# ENGI301_Project_Actual.net
KiCad netlist of a schematic drawn in EAGLE
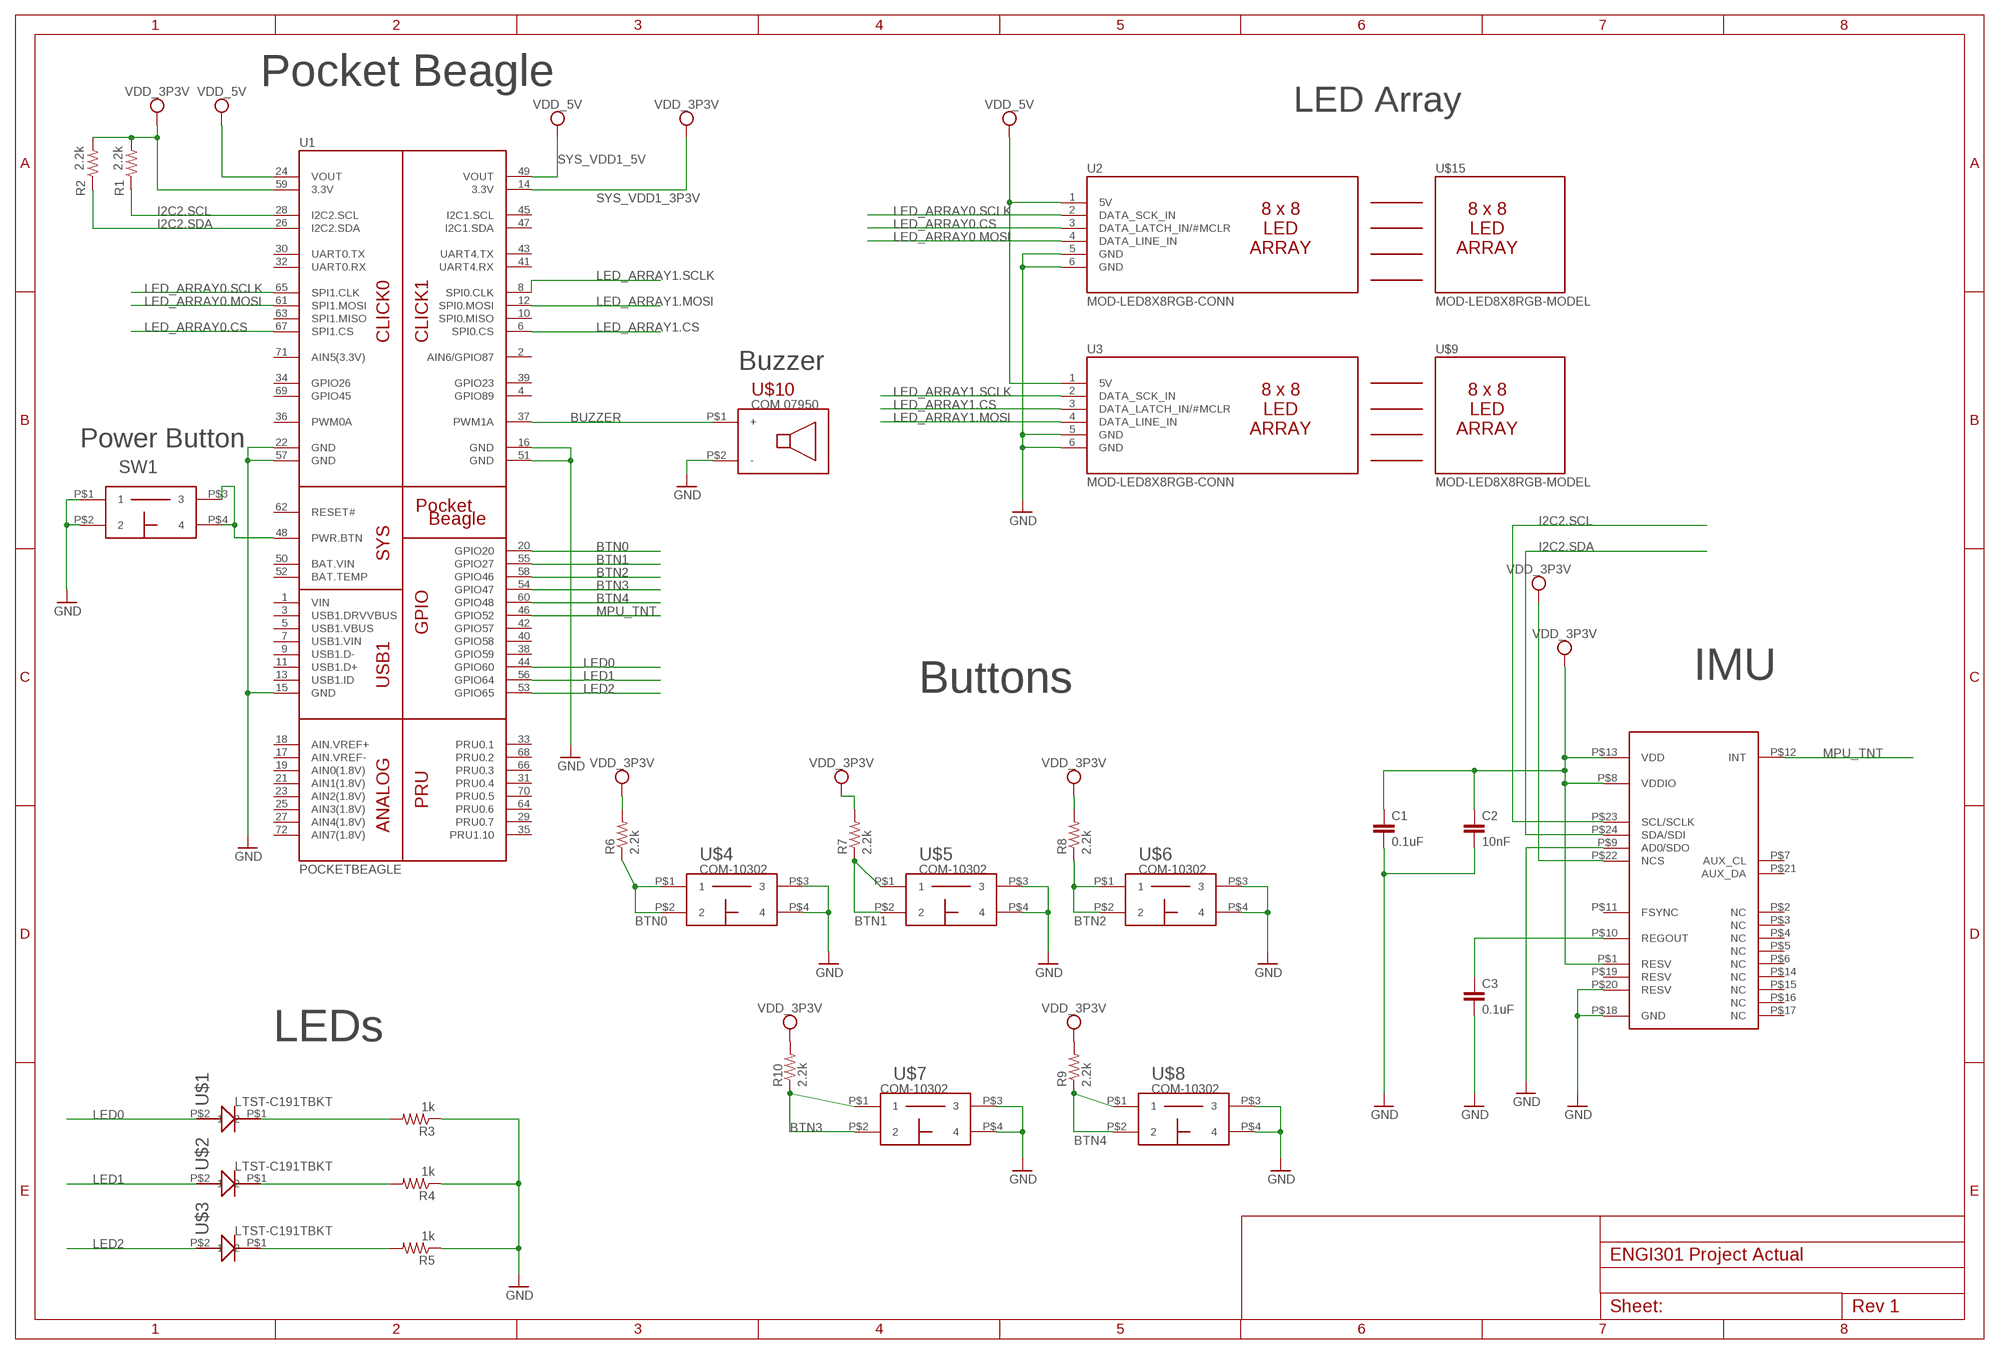
[diagram p0: schematic, sheet 1]

(export (version "E")
  (design (tool "Eeschema 10.0.6"))
  (components
    (comp (ref "C1")
      (value "0.1uF")
      (footprint "eagle-import:C0603")
      (libsource (lib "eagle-import") (part "C_C0603"))
    )
    (comp (ref "C2")
      (value "10nF")
      (footprint "eagle-import:C0603")
      (libsource (lib "eagle-import") (part "C_C0603"))
    )
    (comp (ref "C3")
      (value "0.1uF")
      (footprint "eagle-import:C0603")
      (libsource (lib "eagle-import") (part "C_C0603"))
    )
    (comp (ref "R1")
      (value "2.2k")
      (footprint "eagle-import:R0603")
      (libsource (lib "eagle-import") (part "R_R0603"))
    )
    (comp (ref "R2")
      (value "2.2k")
      (footprint "eagle-import:R0603")
      (libsource (lib "eagle-import") (part "R_R0603"))
    )
    (comp (ref "R3")
      (value "1k")
      (footprint "eagle-import:R0603")
      (libsource (lib "eagle-import") (part "R_R0603"))
    )
    (comp (ref "R4")
      (value "1k")
      (footprint "eagle-import:R0603")
      (libsource (lib "eagle-import") (part "R_R0603"))
    )
    (comp (ref "R5")
      (value "1k")
      (footprint "eagle-import:R0603")
      (libsource (lib "eagle-import") (part "R_R0603"))
    )
    (comp (ref "R6")
      (value "2.2k")
      (footprint "eagle-import:R0603")
      (libsource (lib "eagle-import") (part "R_R0603"))
    )
    (comp (ref "R7")
      (value "2.2k")
      (footprint "eagle-import:R0603")
      (libsource (lib "eagle-import") (part "R_R0603"))
    )
    (comp (ref "R8")
      (value "2.2k")
      (footprint "eagle-import:R0603")
      (libsource (lib "eagle-import") (part "R_R0603"))
    )
    (comp (ref "R9")
      (value "2.2k")
      (footprint "eagle-import:R0603")
      (libsource (lib "eagle-import") (part "R_R0603"))
    )
    (comp (ref "R10")
      (value "2.2k")
      (footprint "eagle-import:R0603")
      (libsource (lib "eagle-import") (part "R_R0603"))
    )
    (comp (ref "SW1")
      (value "BUTTON")
      (footprint "eagle-import:BUTTON")
      (libsource (lib "eagle-import") (part "BUTTON"))
    )
    (comp (ref "U$1")
      (value "LED")
      (footprint "eagle-import:LED")
      (libsource (lib "eagle-import") (part "LED"))
    )
    (comp (ref "U$2")
      (value "LED")
      (footprint "eagle-import:LED")
      (libsource (lib "eagle-import") (part "LED"))
    )
    (comp (ref "U$3")
      (value "LED")
      (footprint "eagle-import:LED")
      (libsource (lib "eagle-import") (part "LED"))
    )
    (comp (ref "U$4")
      (value "BUTTON")
      (footprint "eagle-import:BUTTON")
      (libsource (lib "eagle-import") (part "BUTTON"))
    )
    (comp (ref "U$5")
      (value "BUTTON")
      (footprint "eagle-import:BUTTON")
      (libsource (lib "eagle-import") (part "BUTTON"))
    )
    (comp (ref "U$6")
      (value "BUTTON")
      (footprint "eagle-import:BUTTON")
      (libsource (lib "eagle-import") (part "BUTTON"))
    )
    (comp (ref "U$7")
      (value "BUTTON")
      (footprint "eagle-import:BUTTON")
      (libsource (lib "eagle-import") (part "BUTTON"))
    )
    (comp (ref "U$8")
      (value "BUTTON")
      (footprint "eagle-import:BUTTON")
      (libsource (lib "eagle-import") (part "BUTTON"))
    )
    (comp (ref "U$10")
      (value "BUZZER")
      (footprint "eagle-import:BUZZER")
      (libsource (lib "eagle-import") (part "BUZZER"))
    )
    (comp (ref "U1")
      (value "POCKETBEAGLE")
      (footprint "eagle-import:POCKETBEAGLE")
      (libsource (lib "eagle-import") (part "POCKETBEAGLE"))
    )
    (comp (ref "U2")
      (value "MOD-LED8X8RGB-CONN")
      (footprint "eagle-import:FE06W")
      (libsource (lib "eagle-import") (part "MOD-LED8X8RGB-CONN"))
    )
    (comp (ref "U3")
      (value "MOD-LED8X8RGB-CONN")
      (footprint "eagle-import:FE06W")
      (libsource (lib "eagle-import") (part "MOD-LED8X8RGB-CONN"))
    )
    (comp (ref "U6")
      (value "MPU-9250")
      (footprint "eagle-import:QFN3")
      (libsource (lib "eagle-import") (part "MPU-9250"))
    )
  )
  (nets
    (net (code "1") (name "/BTN0") (class "Default")
      (node (ref "R6") (pin "1") (pinfunction "1_1") (pintype "passive"))
      (node (ref "U$4") (pin "P$1") (pinfunction "1_P$1") (pintype "bidirectional"))
      (node (ref "U$4") (pin "P$2") (pinfunction "2_P$2") (pintype "bidirectional"))
      (node (ref "U1") (pin "20") (pinfunction "GPIO20_20") (pintype "bidirectional"))
    )
    (net (code "2") (name "/BTN1") (class "Default")
      (node (ref "R7") (pin "1") (pinfunction "1_1") (pintype "passive"))
      (node (ref "U$5") (pin "P$1") (pinfunction "1_P$1") (pintype "bidirectional"))
      (node (ref "U$5") (pin "P$2") (pinfunction "2_P$2") (pintype "bidirectional"))
      (node (ref "U1") (pin "55") (pinfunction "GPIO27_55") (pintype "bidirectional"))
    )
    (net (code "3") (name "/BTN2") (class "Default")
      (node (ref "R8") (pin "1") (pinfunction "1_1") (pintype "passive"))
      (node (ref "U$6") (pin "P$1") (pinfunction "1_P$1") (pintype "bidirectional"))
      (node (ref "U$6") (pin "P$2") (pinfunction "2_P$2") (pintype "bidirectional"))
      (node (ref "U1") (pin "58") (pinfunction "GPIO46_58") (pintype "bidirectional"))
    )
    (net (code "4") (name "/BTN3") (class "Default")
      (node (ref "R10") (pin "1") (pinfunction "1_1") (pintype "passive"))
      (node (ref "U$7") (pin "P$1") (pinfunction "1_P$1") (pintype "bidirectional"))
      (node (ref "U$7") (pin "P$2") (pinfunction "2_P$2") (pintype "bidirectional"))
      (node (ref "U1") (pin "54") (pinfunction "GPIO47_54") (pintype "bidirectional"))
    )
    (net (code "5") (name "/BTN4") (class "Default")
      (node (ref "R9") (pin "1") (pinfunction "1_1") (pintype "passive"))
      (node (ref "U$8") (pin "P$1") (pinfunction "1_P$1") (pintype "bidirectional"))
      (node (ref "U$8") (pin "P$2") (pinfunction "2_P$2") (pintype "bidirectional"))
      (node (ref "U1") (pin "60") (pinfunction "GPIO48_60") (pintype "bidirectional"))
    )
    (net (code "6") (name "/BUZZER") (class "Default")
      (node (ref "U$10") (pin "P$1") (pinfunction "+_P$1") (pintype "bidirectional"))
      (node (ref "U1") (pin "37") (pinfunction "PWM1A_37") (pintype "bidirectional"))
    )
    (net (code "7") (name "/I2C2.SCL") (class "Default")
      (node (ref "R1") (pin "1") (pinfunction "1_1") (pintype "passive"))
      (node (ref "U1") (pin "28") (pinfunction "I2C2.SCL_28") (pintype "bidirectional"))
      (node (ref "U6") (pin "P$23") (pinfunction "SCL/SCLK_P$23") (pintype "bidirectional"))
    )
    (net (code "8") (name "/I2C2.SDA") (class "Default")
      (node (ref "R2") (pin "1") (pinfunction "1_1") (pintype "passive"))
      (node (ref "U1") (pin "26") (pinfunction "I2C2.SDA_26") (pintype "bidirectional"))
      (node (ref "U6") (pin "P$24") (pinfunction "SDA/SDI_P$24") (pintype "bidirectional"))
    )
    (net (code "9") (name "/LED0") (class "Default")
      (node (ref "U$1") (pin "P$2") (pinfunction "2_P$2") (pintype "bidirectional"))
      (node (ref "U1") (pin "44") (pinfunction "GPIO60_44") (pintype "bidirectional"))
    )
    (net (code "10") (name "/LED1") (class "Default")
      (node (ref "U$2") (pin "P$2") (pinfunction "2_P$2") (pintype "bidirectional"))
      (node (ref "U1") (pin "56") (pinfunction "GPIO64_56") (pintype "bidirectional"))
    )
    (net (code "11") (name "/LED2") (class "Default")
      (node (ref "U$3") (pin "P$2") (pinfunction "2_P$2") (pintype "bidirectional"))
      (node (ref "U1") (pin "53") (pinfunction "GPIO65_53") (pintype "bidirectional"))
    )
    (net (code "12") (name "/LED_ARRAY0.CS") (class "Default")
      (node (ref "U1") (pin "67") (pinfunction "SPI1.CS_67") (pintype "bidirectional"))
      (node (ref "U2") (pin "3") (pinfunction "DATA_LATCH_IN/#MCLR_3") (pintype "bidirectional"))
    )
    (net (code "13") (name "/LED_ARRAY0.MOSI") (class "Default")
      (node (ref "U1") (pin "61") (pinfunction "SPI1.MOSI_61") (pintype "bidirectional"))
      (node (ref "U2") (pin "4") (pinfunction "DATA_LINE_IN_4") (pintype "bidirectional"))
    )
    (net (code "14") (name "/LED_ARRAY0.SCLK") (class "Default")
      (node (ref "U1") (pin "65") (pinfunction "SPI1.CLK_65") (pintype "bidirectional"))
      (node (ref "U2") (pin "2") (pinfunction "DATA_SCK_IN_2") (pintype "bidirectional"))
    )
    (net (code "15") (name "/LED_ARRAY1.CS") (class "Default")
      (node (ref "U1") (pin "6") (pinfunction "SPI0.CS_6") (pintype "bidirectional"))
      (node (ref "U3") (pin "3") (pinfunction "DATA_LATCH_IN/#MCLR_3") (pintype "bidirectional"))
    )
    (net (code "16") (name "/LED_ARRAY1.MOSI") (class "Default")
      (node (ref "U1") (pin "12") (pinfunction "SPI0.MOSI_12") (pintype "bidirectional"))
      (node (ref "U3") (pin "4") (pinfunction "DATA_LINE_IN_4") (pintype "bidirectional"))
    )
    (net (code "17") (name "/LED_ARRAY1.SCLK") (class "Default")
      (node (ref "U1") (pin "8") (pinfunction "SPI0.CLK_8") (pintype "bidirectional"))
      (node (ref "U3") (pin "2") (pinfunction "DATA_SCK_IN_2") (pintype "bidirectional"))
    )
    (net (code "18") (name "/MPU_TNT") (class "Default")
      (node (ref "U1") (pin "46") (pinfunction "GPIO52_46") (pintype "bidirectional"))
      (node (ref "U6") (pin "P$12") (pinfunction "INT_P$12") (pintype "bidirectional"))
    )
    (net (code "19") (name "GND") (class "Default")
      (node (ref "C1") (pin "2") (pinfunction "2_2") (pintype "passive"))
      (node (ref "C2") (pin "2") (pinfunction "2_2") (pintype "passive"))
      (node (ref "C3") (pin "2") (pinfunction "2_2") (pintype "passive"))
      (node (ref "R3") (pin "1") (pinfunction "1_1") (pintype "passive"))
      (node (ref "R4") (pin "1") (pinfunction "1_1") (pintype "passive"))
      (node (ref "R5") (pin "1") (pinfunction "1_1") (pintype "passive"))
      (node (ref "SW1") (pin "P$1") (pinfunction "1_P$1") (pintype "bidirectional"))
      (node (ref "SW1") (pin "P$2") (pinfunction "2_P$2") (pintype "bidirectional"))
      (node (ref "U$10") (pin "P$2") (pinfunction "-_P$2") (pintype "bidirectional"))
      (node (ref "U$4") (pin "P$3") (pinfunction "3_P$3") (pintype "bidirectional"))
      (node (ref "U$4") (pin "P$4") (pinfunction "4_P$4") (pintype "bidirectional"))
      (node (ref "U$5") (pin "P$3") (pinfunction "3_P$3") (pintype "bidirectional"))
      (node (ref "U$5") (pin "P$4") (pinfunction "4_P$4") (pintype "bidirectional"))
      (node (ref "U$6") (pin "P$3") (pinfunction "3_P$3") (pintype "bidirectional"))
      (node (ref "U$6") (pin "P$4") (pinfunction "4_P$4") (pintype "bidirectional"))
      (node (ref "U$7") (pin "P$3") (pinfunction "3_P$3") (pintype "bidirectional"))
      (node (ref "U$7") (pin "P$4") (pinfunction "4_P$4") (pintype "bidirectional"))
      (node (ref "U$8") (pin "P$3") (pinfunction "3_P$3") (pintype "bidirectional"))
      (node (ref "U$8") (pin "P$4") (pinfunction "4_P$4") (pintype "bidirectional"))
      (node (ref "U1") (pin "15") (pinfunction "GND_15") (pintype "bidirectional"))
      (node (ref "U1") (pin "16") (pinfunction "GND_16") (pintype "bidirectional"))
      (node (ref "U1") (pin "22") (pinfunction "GND_22") (pintype "bidirectional"))
      (node (ref "U1") (pin "51") (pinfunction "GND_51") (pintype "bidirectional"))
      (node (ref "U1") (pin "57") (pinfunction "GND_57") (pintype "bidirectional"))
      (node (ref "U2") (pin "5") (pinfunction "GND_5") (pintype "bidirectional"))
      (node (ref "U2") (pin "6") (pinfunction "GND_6") (pintype "bidirectional"))
      (node (ref "U3") (pin "5") (pinfunction "GND_5") (pintype "bidirectional"))
      (node (ref "U3") (pin "6") (pinfunction "GND_6") (pintype "bidirectional"))
      (node (ref "U6") (pin "P$18") (pinfunction "GND_P$18") (pintype "bidirectional"))
      (node (ref "U6") (pin "P$20") (pinfunction "RESV_P$20") (pintype "bidirectional"))
      (node (ref "U6") (pin "P$9") (pinfunction "AD0/SDO_P$9") (pintype "bidirectional"))
    )
    (net (code "20") (name "Net-(SW1-3)") (class "Default")
      (node (ref "SW1") (pin "P$3") (pinfunction "3_P$3") (pintype "bidirectional"))
      (node (ref "SW1") (pin "P$4") (pinfunction "4_P$4") (pintype "bidirectional"))
      (node (ref "U1") (pin "48") (pinfunction "PWR.BTN_48") (pintype "bidirectional"))
    )
    (net (code "21") (name "Net-(U$1-1)") (class "Default")
      (node (ref "R3") (pin "2") (pinfunction "2_2") (pintype "passive"))
      (node (ref "U$1") (pin "P$1") (pinfunction "1_P$1") (pintype "bidirectional"))
    )
    (net (code "22") (name "Net-(U$2-1)") (class "Default")
      (node (ref "R4") (pin "2") (pinfunction "2_2") (pintype "passive"))
      (node (ref "U$2") (pin "P$1") (pinfunction "1_P$1") (pintype "bidirectional"))
    )
    (net (code "23") (name "Net-(U$3-1)") (class "Default")
      (node (ref "R5") (pin "2") (pinfunction "2_2") (pintype "passive"))
      (node (ref "U$3") (pin "P$1") (pinfunction "1_P$1") (pintype "bidirectional"))
    )
    (net (code "24") (name "Net-(U6-REGOUT)") (class "Default")
      (node (ref "C3") (pin "1") (pinfunction "1_1") (pintype "passive"))
      (node (ref "U6") (pin "P$10") (pinfunction "REGOUT_P$10") (pintype "bidirectional"))
    )
    (net (code "25") (name "VDD_3P3V") (class "Default")
      (node (ref "C1") (pin "1") (pinfunction "1_1") (pintype "passive"))
      (node (ref "C2") (pin "1") (pinfunction "1_1") (pintype "passive"))
      (node (ref "R1") (pin "2") (pinfunction "2_2") (pintype "passive"))
      (node (ref "R10") (pin "2") (pinfunction "2_2") (pintype "passive"))
      (node (ref "R2") (pin "2") (pinfunction "2_2") (pintype "passive"))
      (node (ref "R6") (pin "2") (pinfunction "2_2") (pintype "passive"))
      (node (ref "R7") (pin "2") (pinfunction "2_2") (pintype "passive"))
      (node (ref "R8") (pin "2") (pinfunction "2_2") (pintype "passive"))
      (node (ref "R9") (pin "2") (pinfunction "2_2") (pintype "passive"))
      (node (ref "U1") (pin "14") (pinfunction "3.3V_14") (pintype "bidirectional"))
      (node (ref "U1") (pin "59") (pinfunction "3.3V_59") (pintype "bidirectional"))
      (node (ref "U6") (pin "P$1") (pinfunction "RESV_P$1") (pintype "bidirectional"))
      (node (ref "U6") (pin "P$13") (pinfunction "VDD_P$13") (pintype "bidirectional"))
      (node (ref "U6") (pin "P$22") (pinfunction "NCS_P$22") (pintype "bidirectional"))
      (node (ref "U6") (pin "P$8") (pinfunction "VDDIO_P$8") (pintype "bidirectional"))
    )
    (net (code "26") (name "VDD_5V") (class "Default")
      (node (ref "U1") (pin "24") (pinfunction "VOUT_24") (pintype "bidirectional"))
      (node (ref "U1") (pin "49") (pinfunction "VOUT_49") (pintype "bidirectional"))
      (node (ref "U2") (pin "1") (pinfunction "5V_1") (pintype "bidirectional"))
      (node (ref "U3") (pin "1") (pinfunction "5V_1") (pintype "bidirectional"))
    )
    (net (code "27") (name "unconnected-(U1-AIN.VREF+-Pad18)") (class "Default")
      (node (ref "U1") (pin "18") (pinfunction "AIN.VREF+_18") (pintype "bidirectional"))
    )
    (net (code "28") (name "unconnected-(U1-AIN.VREF--Pad17)") (class "Default")
      (node (ref "U1") (pin "17") (pinfunction "AIN.VREF-_17") (pintype "bidirectional"))
    )
    (net (code "29") (name "unconnected-(U1-AIN0(1.8V)-Pad19)") (class "Default")
      (node (ref "U1") (pin "19") (pinfunction "AIN0(1.8V)_19") (pintype "bidirectional"))
    )
    (net (code "30") (name "unconnected-(U1-AIN1(1.8V)-Pad21)") (class "Default")
      (node (ref "U1") (pin "21") (pinfunction "AIN1(1.8V)_21") (pintype "bidirectional"))
    )
    (net (code "31") (name "unconnected-(U1-AIN2(1.8V)-Pad23)") (class "Default")
      (node (ref "U1") (pin "23") (pinfunction "AIN2(1.8V)_23") (pintype "bidirectional"))
    )
    (net (code "32") (name "unconnected-(U1-AIN3(1.8V)-Pad25)") (class "Default")
      (node (ref "U1") (pin "25") (pinfunction "AIN3(1.8V)_25") (pintype "bidirectional"))
    )
    (net (code "33") (name "unconnected-(U1-AIN4(1.8V)-Pad27)") (class "Default")
      (node (ref "U1") (pin "27") (pinfunction "AIN4(1.8V)_27") (pintype "bidirectional"))
    )
    (net (code "34") (name "unconnected-(U1-AIN5(3.3V)-Pad71)") (class "Default")
      (node (ref "U1") (pin "71") (pinfunction "AIN5(3.3V)_71") (pintype "bidirectional"))
    )
    (net (code "35") (name "unconnected-(U1-AIN6{slash}GPIO87-Pad2)") (class "Default")
      (node (ref "U1") (pin "2") (pinfunction "AIN6/GPIO87_2") (pintype "bidirectional"))
    )
    (net (code "36") (name "unconnected-(U1-AIN7(1.8V)-Pad72)") (class "Default")
      (node (ref "U1") (pin "72") (pinfunction "AIN7(1.8V)_72") (pintype "bidirectional"))
    )
    (net (code "37") (name "unconnected-(U1-BAT.TEMP-Pad52)") (class "Default")
      (node (ref "U1") (pin "52") (pinfunction "BAT.TEMP_52") (pintype "bidirectional"))
    )
    (net (code "38") (name "unconnected-(U1-BAT.VIN-Pad50)") (class "Default")
      (node (ref "U1") (pin "50") (pinfunction "BAT.VIN_50") (pintype "bidirectional"))
    )
    (net (code "39") (name "unconnected-(U1-GPIO23-Pad39)") (class "Default")
      (node (ref "U1") (pin "39") (pinfunction "GPIO23_39") (pintype "bidirectional"))
    )
    (net (code "40") (name "unconnected-(U1-GPIO26-Pad34)") (class "Default")
      (node (ref "U1") (pin "34") (pinfunction "GPIO26_34") (pintype "bidirectional"))
    )
    (net (code "41") (name "unconnected-(U1-GPIO45-Pad69)") (class "Default")
      (node (ref "U1") (pin "69") (pinfunction "GPIO45_69") (pintype "bidirectional"))
    )
    (net (code "42") (name "unconnected-(U1-GPIO57-Pad42)") (class "Default")
      (node (ref "U1") (pin "42") (pinfunction "GPIO57_42") (pintype "bidirectional"))
    )
    (net (code "43") (name "unconnected-(U1-GPIO58-Pad40)") (class "Default")
      (node (ref "U1") (pin "40") (pinfunction "GPIO58_40") (pintype "bidirectional"))
    )
    (net (code "44") (name "unconnected-(U1-GPIO59-Pad38)") (class "Default")
      (node (ref "U1") (pin "38") (pinfunction "GPIO59_38") (pintype "bidirectional"))
    )
    (net (code "45") (name "unconnected-(U1-GPIO89-Pad4)") (class "Default")
      (node (ref "U1") (pin "4") (pinfunction "GPIO89_4") (pintype "bidirectional"))
    )
    (net (code "46") (name "unconnected-(U1-I2C1.SCL-Pad45)") (class "Default")
      (node (ref "U1") (pin "45") (pinfunction "I2C1.SCL_45") (pintype "bidirectional"))
    )
    (net (code "47") (name "unconnected-(U1-I2C1.SDA-Pad47)") (class "Default")
      (node (ref "U1") (pin "47") (pinfunction "I2C1.SDA_47") (pintype "bidirectional"))
    )
    (net (code "48") (name "unconnected-(U1-PRU0.1-Pad33)") (class "Default")
      (node (ref "U1") (pin "33") (pinfunction "PRU0.1_33") (pintype "bidirectional"))
    )
    (net (code "49") (name "unconnected-(U1-PRU0.2-Pad68)") (class "Default")
      (node (ref "U1") (pin "68") (pinfunction "PRU0.2_68") (pintype "bidirectional"))
    )
    (net (code "50") (name "unconnected-(U1-PRU0.3-Pad66)") (class "Default")
      (node (ref "U1") (pin "66") (pinfunction "PRU0.3_66") (pintype "bidirectional"))
    )
    (net (code "51") (name "unconnected-(U1-PRU0.4-Pad31)") (class "Default")
      (node (ref "U1") (pin "31") (pinfunction "PRU0.4_31") (pintype "bidirectional"))
    )
    (net (code "52") (name "unconnected-(U1-PRU0.5-Pad70)") (class "Default")
      (node (ref "U1") (pin "70") (pinfunction "PRU0.5_70") (pintype "bidirectional"))
    )
    (net (code "53") (name "unconnected-(U1-PRU0.6-Pad64)") (class "Default")
      (node (ref "U1") (pin "64") (pinfunction "PRU0.6_64") (pintype "bidirectional"))
    )
    (net (code "54") (name "unconnected-(U1-PRU0.7-Pad29)") (class "Default")
      (node (ref "U1") (pin "29") (pinfunction "PRU0.7_29") (pintype "bidirectional"))
    )
    (net (code "55") (name "unconnected-(U1-PRU1.10-Pad35)") (class "Default")
      (node (ref "U1") (pin "35") (pinfunction "PRU1.10_35") (pintype "bidirectional"))
    )
    (net (code "56") (name "unconnected-(U1-PWM0A-Pad36)") (class "Default")
      (node (ref "U1") (pin "36") (pinfunction "PWM0A_36") (pintype "bidirectional"))
    )
    (net (code "57") (name "unconnected-(U1-RESET#-Pad62)") (class "Default")
      (node (ref "U1") (pin "62") (pinfunction "RESET#_62") (pintype "bidirectional"))
    )
    (net (code "58") (name "unconnected-(U1-SPI0.MISO-Pad10)") (class "Default")
      (node (ref "U1") (pin "10") (pinfunction "SPI0.MISO_10") (pintype "bidirectional"))
    )
    (net (code "59") (name "unconnected-(U1-SPI1.MISO-Pad63)") (class "Default")
      (node (ref "U1") (pin "63") (pinfunction "SPI1.MISO_63") (pintype "bidirectional"))
    )
    (net (code "60") (name "unconnected-(U1-UART0.RX-Pad32)") (class "Default")
      (node (ref "U1") (pin "32") (pinfunction "UART0.RX_32") (pintype "bidirectional"))
    )
    (net (code "61") (name "unconnected-(U1-UART0.TX-Pad30)") (class "Default")
      (node (ref "U1") (pin "30") (pinfunction "UART0.TX_30") (pintype "bidirectional"))
    )
    (net (code "62") (name "unconnected-(U1-UART4.RX-Pad41)") (class "Default")
      (node (ref "U1") (pin "41") (pinfunction "UART4.RX_41") (pintype "bidirectional"))
    )
    (net (code "63") (name "unconnected-(U1-UART4.TX-Pad43)") (class "Default")
      (node (ref "U1") (pin "43") (pinfunction "UART4.TX_43") (pintype "bidirectional"))
    )
    (net (code "64") (name "unconnected-(U1-USB1.D+-Pad11)") (class "Default")
      (node (ref "U1") (pin "11") (pinfunction "USB1.D+_11") (pintype "bidirectional"))
    )
    (net (code "65") (name "unconnected-(U1-USB1.D--Pad9)") (class "Default")
      (node (ref "U1") (pin "9") (pinfunction "USB1.D-_9") (pintype "bidirectional"))
    )
    (net (code "66") (name "unconnected-(U1-USB1.DRVVBUS-Pad3)") (class "Default")
      (node (ref "U1") (pin "3") (pinfunction "USB1.DRVVBUS_3") (pintype "bidirectional"))
    )
    (net (code "67") (name "unconnected-(U1-USB1.ID-Pad13)") (class "Default")
      (node (ref "U1") (pin "13") (pinfunction "USB1.ID_13") (pintype "bidirectional"))
    )
    (net (code "68") (name "unconnected-(U1-USB1.VBUS-Pad5)") (class "Default")
      (node (ref "U1") (pin "5") (pinfunction "USB1.VBUS_5") (pintype "bidirectional"))
    )
    (net (code "69") (name "unconnected-(U1-USB1.VIN-Pad7)") (class "Default")
      (node (ref "U1") (pin "7") (pinfunction "USB1.VIN_7") (pintype "bidirectional"))
    )
    (net (code "70") (name "unconnected-(U1-VIN-Pad1)") (class "Default")
      (node (ref "U1") (pin "1") (pinfunction "VIN_1") (pintype "bidirectional"))
    )
    (net (code "71") (name "unconnected-(U6-AUX_CL-PadP$7)") (class "Default")
      (node (ref "U6") (pin "P$7") (pinfunction "AUX_CL_P$7") (pintype "bidirectional"))
    )
    (net (code "72") (name "unconnected-(U6-AUX_DA-PadP$21)") (class "Default")
      (node (ref "U6") (pin "P$21") (pinfunction "AUX_DA_P$21") (pintype "bidirectional"))
    )
    (net (code "73") (name "unconnected-(U6-FSYNC-PadP$11)") (class "Default")
      (node (ref "U6") (pin "P$11") (pinfunction "FSYNC_P$11") (pintype "bidirectional"))
    )
    (net (code "74") (name "unconnected-(U6-NC-PadP$2)") (class "Default")
      (node (ref "U6") (pin "P$2") (pinfunction "NC_P$2") (pintype "bidirectional"))
    )
    (net (code "75") (name "unconnected-(U6-NC-PadP$3)") (class "Default")
      (node (ref "U6") (pin "P$3") (pinfunction "NC_P$3") (pintype "bidirectional"))
    )
    (net (code "76") (name "unconnected-(U6-NC-PadP$4)") (class "Default")
      (node (ref "U6") (pin "P$4") (pinfunction "NC_P$4") (pintype "bidirectional"))
    )
    (net (code "77") (name "unconnected-(U6-NC-PadP$5)") (class "Default")
      (node (ref "U6") (pin "P$5") (pinfunction "NC_P$5") (pintype "bidirectional"))
    )
    (net (code "78") (name "unconnected-(U6-NC-PadP$6)") (class "Default")
      (node (ref "U6") (pin "P$6") (pinfunction "NC_P$6") (pintype "bidirectional"))
    )
    (net (code "79") (name "unconnected-(U6-NC-PadP$14)") (class "Default")
      (node (ref "U6") (pin "P$14") (pinfunction "NC_P$14") (pintype "bidirectional"))
    )
    (net (code "80") (name "unconnected-(U6-NC-PadP$15)") (class "Default")
      (node (ref "U6") (pin "P$15") (pinfunction "NC_P$15") (pintype "bidirectional"))
    )
    (net (code "81") (name "unconnected-(U6-NC-PadP$16)") (class "Default")
      (node (ref "U6") (pin "P$16") (pinfunction "NC_P$16") (pintype "bidirectional"))
    )
    (net (code "82") (name "unconnected-(U6-NC-PadP$17)") (class "Default")
      (node (ref "U6") (pin "P$17") (pinfunction "NC_P$17") (pintype "bidirectional"))
    )
    (net (code "83") (name "unconnected-(U6-RESV-PadP$19)") (class "Default")
      (node (ref "U6") (pin "P$19") (pinfunction "RESV_P$19") (pintype "bidirectional"))
    )
  )
)
